# 555_timer_2021-06-11.net
KiCad netlist of a schematic drawn in EasyEDA
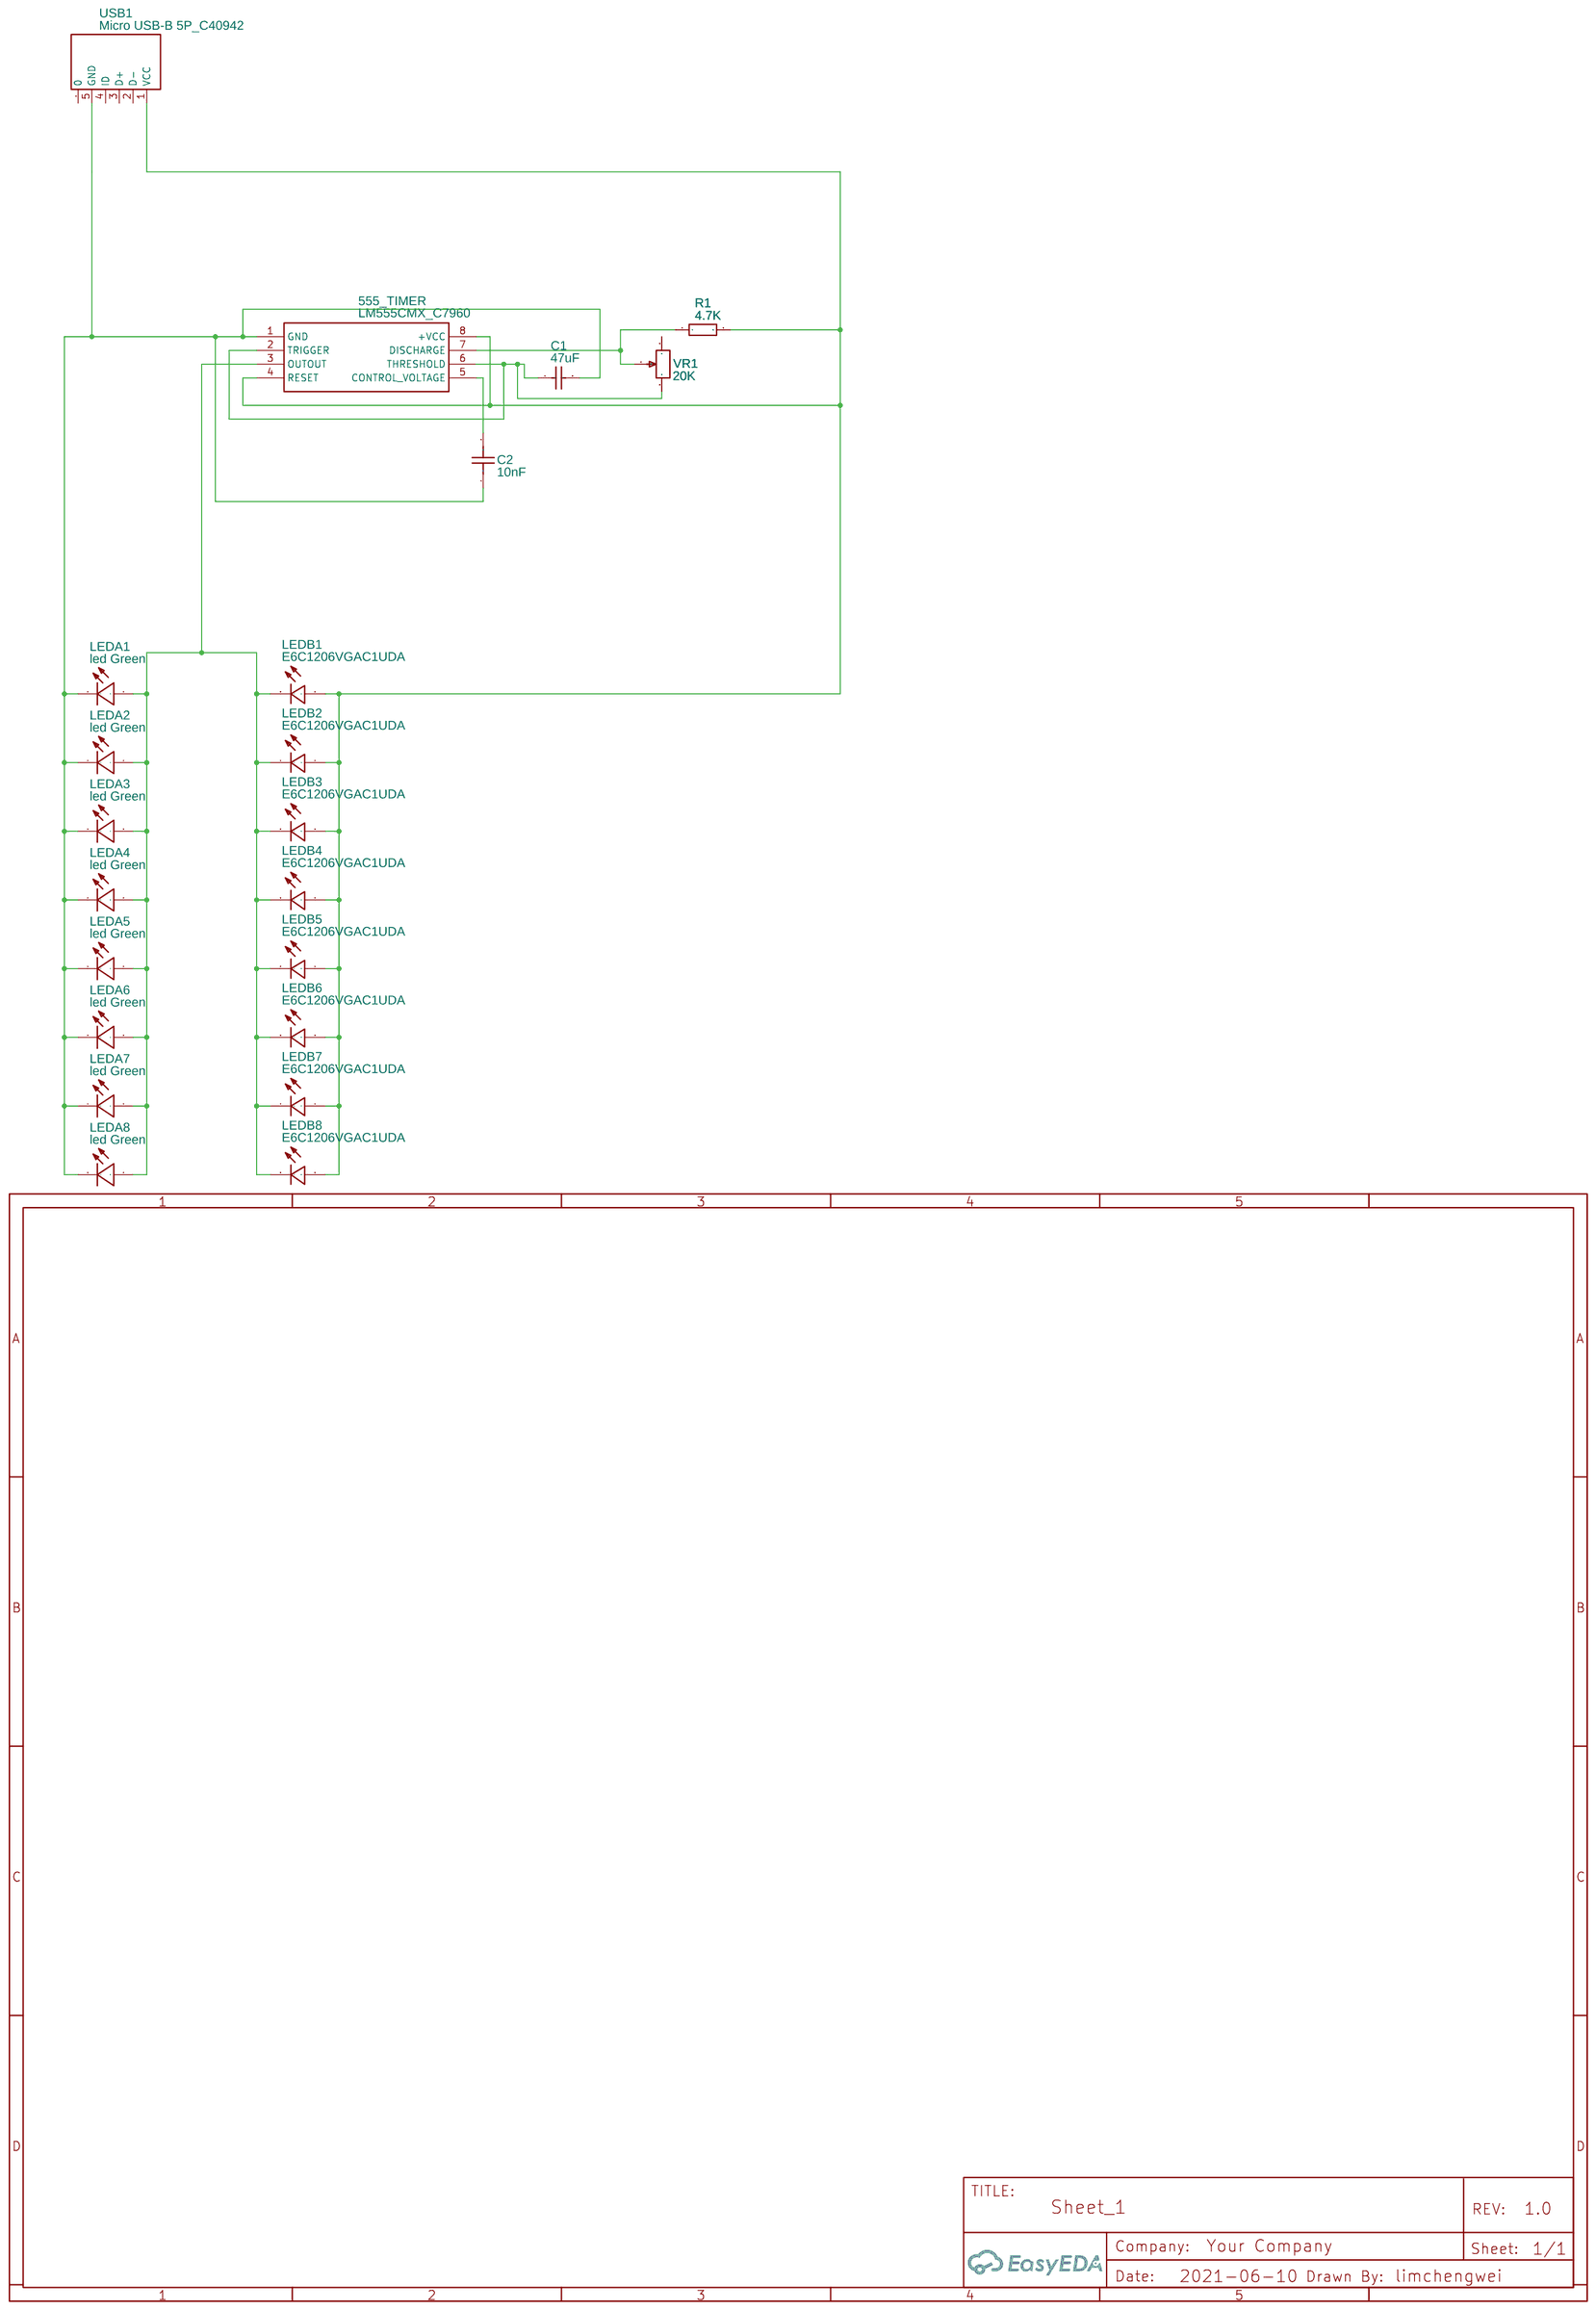
[diagram p0: schematic sheet]

(export (version "E")
  (design (tool "Eeschema 10.0.6"))
  (components
    (comp (ref "555_TIMER")
      (value "LM555CMX_C7960")
      (fields (field (name "BOM_Manufacturer Part") "LM555CMX") (field (name "BOM_Supplier Part") "C7960"))
      (libsource (lib "") (part "LM555CMX_C7960"))
    )
    (comp (ref "C1")
      (value "47uF")
      (fields
        (field (name "BOM_Manufacturer Part") "CL32A476MQJNNWE")
        (field (name "BOM_Supplier Part") "C12605")
      )
      (libsource (lib "") (part "CL32A476MQJNNWE"))
    )
    (comp (ref "C2")
      (value "10nF")
      (fields
        (field (name "BOM_Manufacturer Part") "GCM32D7U2J103JX01L")
        (field (name "BOM_Supplier Part") "C161278")
      )
      (libsource (lib "") (part "GCM32D7U2J103JX01L"))
    )
    (comp (ref "LEDA1")
      (value "led Green")
      (fields (field (name "BOM_Supplier Part") "C14641"))
      (libsource (lib "") (part "led Green"))
    )
    (comp (ref "LEDA2")
      (value "led Green")
      (fields (field (name "BOM_Supplier Part") "C14641"))
      (libsource (lib "") (part "led Green"))
    )
    (comp (ref "LEDA3")
      (value "led Green")
      (fields (field (name "BOM_Supplier Part") "C14641"))
      (libsource (lib "") (part "led Green"))
    )
    (comp (ref "LEDA4")
      (value "led Green")
      (fields (field (name "BOM_Supplier Part") "C14641"))
      (libsource (lib "") (part "led Green"))
    )
    (comp (ref "LEDA5")
      (value "led Green")
      (fields (field (name "BOM_Supplier Part") "C14641"))
      (libsource (lib "") (part "led Green"))
    )
    (comp (ref "LEDA6")
      (value "led Green")
      (fields (field (name "BOM_Supplier Part") "C14641"))
      (libsource (lib "") (part "led Green"))
    )
    (comp (ref "LEDA7")
      (value "led Green")
      (fields (field (name "BOM_Supplier Part") "C14641"))
      (libsource (lib "") (part "led Green"))
    )
    (comp (ref "LEDA8")
      (value "led Green")
      (fields (field (name "BOM_Supplier Part") "C14641"))
      (libsource (lib "") (part "led Green"))
    )
    (comp (ref "LEDB1")
      (value "E6C1206VGAC1UDA")
      (fields (field (name "BOM_Supplier Part") "C375461"))
      (libsource (lib "") (part "E6C1206VGAC1UDA"))
    )
    (comp (ref "LEDB2")
      (value "E6C1206VGAC1UDA")
      (fields (field (name "BOM_Supplier Part") "C375461"))
      (libsource (lib "") (part "E6C1206VGAC1UDA"))
    )
    (comp (ref "LEDB3")
      (value "E6C1206VGAC1UDA")
      (fields (field (name "BOM_Supplier Part") "C375461"))
      (libsource (lib "") (part "E6C1206VGAC1UDA"))
    )
    (comp (ref "LEDB4")
      (value "E6C1206VGAC1UDA")
      (fields (field (name "BOM_Supplier Part") "C375461"))
      (libsource (lib "") (part "E6C1206VGAC1UDA"))
    )
    (comp (ref "LEDB5")
      (value "E6C1206VGAC1UDA")
      (fields (field (name "BOM_Supplier Part") "C375461"))
      (libsource (lib "") (part "E6C1206VGAC1UDA"))
    )
    (comp (ref "LEDB6")
      (value "E6C1206VGAC1UDA")
      (fields (field (name "BOM_Supplier Part") "C375461"))
      (libsource (lib "") (part "E6C1206VGAC1UDA"))
    )
    (comp (ref "LEDB7")
      (value "E6C1206VGAC1UDA")
      (fields (field (name "BOM_Supplier Part") "C375461"))
      (libsource (lib "") (part "E6C1206VGAC1UDA"))
    )
    (comp (ref "LEDB8")
      (value "E6C1206VGAC1UDA")
      (fields (field (name "BOM_Supplier Part") "C375461"))
      (libsource (lib "") (part "E6C1206VGAC1UDA"))
    )
    (comp (ref "R1")
      (value "4.7K")
      (fields
        (field (name "BOM_Manufacturer Part") "1210W3F4701T5E")
        (field (name "BOM_Supplier Part") "C52443")
      )
      (libsource (lib "") (part "1210W3F4701T5E"))
    )
    (comp (ref "USB1")
      (value "Micro USB-B 5P_C40942")
      (fields (field (name "BOM_Supplier Part") "C40942"))
      (libsource (lib "") (part "Micro USB-B 5P_C40942"))
    )
    (comp (ref "VR1")
      (value "20K")
      (fields
        (field (name "BOM_Manufacturer Part") "3314J-1-203E")
        (field (name "BOM_Supplier Part") "C55069")
      )
      (libsource (lib "") (part "3314J-1-203E"))
    )
  )
  (nets
    (net (code "1") (name "Net-(555_TIMER-+VCC)") (class "Default")
      (node (ref "555_TIMER") (pin "4") (pinfunction "RESET_4") (pintype "unspecified"))
      (node (ref "555_TIMER") (pin "8") (pinfunction "+VCC_8") (pintype "passive"))
      (node (ref "LEDB1") (pin "1") (pinfunction "+_1") (pintype "unspecified"))
      (node (ref "LEDB2") (pin "1") (pinfunction "+_1") (pintype "unspecified"))
      (node (ref "LEDB3") (pin "1") (pinfunction "+_1") (pintype "unspecified"))
      (node (ref "LEDB4") (pin "1") (pinfunction "+_1") (pintype "unspecified"))
      (node (ref "LEDB5") (pin "1") (pinfunction "+_1") (pintype "unspecified"))
      (node (ref "LEDB6") (pin "1") (pinfunction "+_1") (pintype "unspecified"))
      (node (ref "LEDB7") (pin "1") (pinfunction "+_1") (pintype "unspecified"))
      (node (ref "LEDB8") (pin "1") (pinfunction "+_1") (pintype "unspecified"))
      (node (ref "R1") (pin "2") (pinfunction "2_2") (pintype "input"))
      (node (ref "USB1") (pin "1") (pinfunction "VCC_1") (pintype "input"))
    )
    (net (code "2") (name "Net-(555_TIMER-CONTROL_VOLTAGE)") (class "Default")
      (node (ref "555_TIMER") (pin "5") (pinfunction "CONTROL_VOLTAGE_5") (pintype "unspecified"))
      (node (ref "C2") (pin "2") (pinfunction "2_2") (pintype "unspecified"))
    )
    (net (code "3") (name "Net-(555_TIMER-DISCHARGE)") (class "Default")
      (node (ref "555_TIMER") (pin "7") (pinfunction "DISCHARGE_7") (pintype "unspecified"))
      (node (ref "R1") (pin "1") (pinfunction "1_1") (pintype "input"))
      (node (ref "VR1") (pin "2") (pinfunction "2_2") (pintype "input"))
    )
    (net (code "4") (name "Net-(555_TIMER-GND)") (class "Default")
      (node (ref "555_TIMER") (pin "1") (pinfunction "GND_1") (pintype "passive"))
      (node (ref "C1") (pin "2") (pinfunction "2_2") (pintype "input"))
      (node (ref "C2") (pin "1") (pinfunction "1_1") (pintype "unspecified"))
      (node (ref "LEDA1") (pin "1") (pinfunction "-_1") (pintype "unspecified"))
      (node (ref "LEDA2") (pin "1") (pinfunction "-_1") (pintype "unspecified"))
      (node (ref "LEDA3") (pin "1") (pinfunction "-_1") (pintype "unspecified"))
      (node (ref "LEDA4") (pin "1") (pinfunction "-_1") (pintype "unspecified"))
      (node (ref "LEDA5") (pin "1") (pinfunction "-_1") (pintype "unspecified"))
      (node (ref "LEDA6") (pin "1") (pinfunction "-_1") (pintype "unspecified"))
      (node (ref "LEDA7") (pin "1") (pinfunction "-_1") (pintype "unspecified"))
      (node (ref "LEDA8") (pin "1") (pinfunction "-_1") (pintype "unspecified"))
      (node (ref "USB1") (pin "5") (pinfunction "GND_5") (pintype "input"))
    )
    (net (code "5") (name "Net-(555_TIMER-OUTOUT)") (class "Default")
      (node (ref "555_TIMER") (pin "3") (pinfunction "OUTOUT_3") (pintype "output"))
      (node (ref "LEDA1") (pin "2") (pinfunction "+_2") (pintype "unspecified"))
      (node (ref "LEDA2") (pin "2") (pinfunction "+_2") (pintype "unspecified"))
      (node (ref "LEDA3") (pin "2") (pinfunction "+_2") (pintype "unspecified"))
      (node (ref "LEDA4") (pin "2") (pinfunction "+_2") (pintype "unspecified"))
      (node (ref "LEDA5") (pin "2") (pinfunction "+_2") (pintype "unspecified"))
      (node (ref "LEDA6") (pin "2") (pinfunction "+_2") (pintype "unspecified"))
      (node (ref "LEDA7") (pin "2") (pinfunction "+_2") (pintype "unspecified"))
      (node (ref "LEDA8") (pin "2") (pinfunction "+_2") (pintype "unspecified"))
      (node (ref "LEDB1") (pin "2") (pinfunction "-_2") (pintype "unspecified"))
      (node (ref "LEDB2") (pin "2") (pinfunction "-_2") (pintype "unspecified"))
      (node (ref "LEDB3") (pin "2") (pinfunction "-_2") (pintype "unspecified"))
      (node (ref "LEDB4") (pin "2") (pinfunction "-_2") (pintype "unspecified"))
      (node (ref "LEDB5") (pin "2") (pinfunction "-_2") (pintype "unspecified"))
      (node (ref "LEDB6") (pin "2") (pinfunction "-_2") (pintype "unspecified"))
      (node (ref "LEDB7") (pin "2") (pinfunction "-_2") (pintype "unspecified"))
      (node (ref "LEDB8") (pin "2") (pinfunction "-_2") (pintype "unspecified"))
    )
    (net (code "6") (name "Net-(555_TIMER-THRESHOLD)") (class "Default")
      (node (ref "555_TIMER") (pin "2") (pinfunction "TRIGGER_2") (pintype "unspecified"))
      (node (ref "555_TIMER") (pin "6") (pinfunction "THRESHOLD_6") (pintype "unspecified"))
      (node (ref "C1") (pin "1") (pinfunction "1_1") (pintype "input"))
      (node (ref "VR1") (pin "3") (pinfunction "3_3") (pintype "input"))
    )
    (net (code "7") (name "unconnected-(USB1-D+-Pad3)") (class "Default")
      (node (ref "USB1") (pin "3") (pinfunction "D+_3") (pintype "input"))
    )
    (net (code "8") (name "unconnected-(USB1-D--Pad2)") (class "Default")
      (node (ref "USB1") (pin "2") (pinfunction "D-_2") (pintype "input"))
    )
    (net (code "9") (name "unconnected-(USB1-ID-Pad4)") (class "Default")
      (node (ref "USB1") (pin "4") (pinfunction "ID_4") (pintype "input"))
    )
    (net (code "10") (name "unconnected-(USB1-Pad0)") (class "Default")
      (node (ref "USB1") (pin "0") (pinfunction "0_0") (pintype "input"))
    )
    (net (code "11") (name "unconnected-(VR1-Pad1)") (class "Default")
      (node (ref "VR1") (pin "1") (pinfunction "1_1") (pintype "input"))
    )
  )
)
